# wheatstone.net
KiCad netlist of a schematic drawn in EAGLE
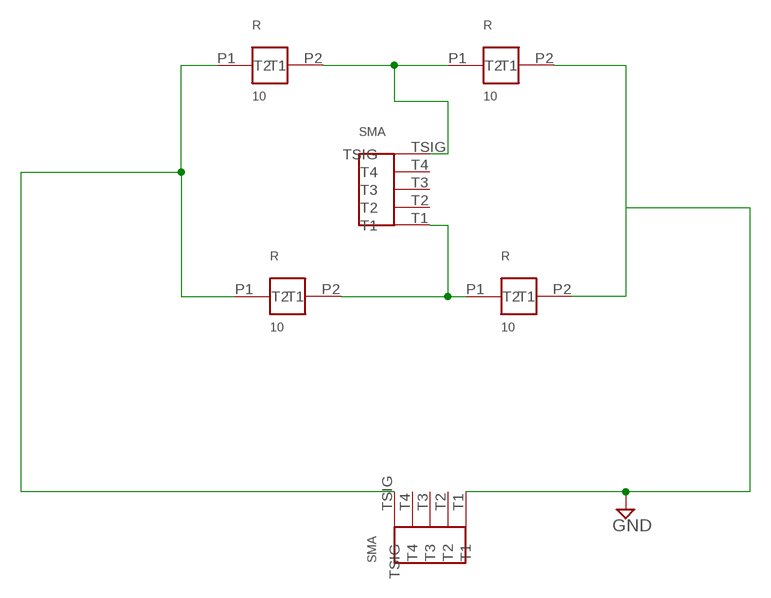
[diagram p0: schematic, sheet 1]

(export (version "E")
  (design (tool "Eeschema 10.0.6"))
  (components
    (comp (ref "U$1")
      (value "0404RESISTORS")
      (footprint "eagle-import:0404RESISTORS")
      (libsource (lib "eagle-import") (part "0404RESISTORS"))
    )
    (comp (ref "U$2")
      (value "0404RESISTORS")
      (footprint "eagle-import:0404RESISTORS")
      (libsource (lib "eagle-import") (part "0404RESISTORS"))
    )
    (comp (ref "U$3")
      (value "0404RESISTORS")
      (footprint "eagle-import:0404RESISTORS")
      (libsource (lib "eagle-import") (part "0404RESISTORS"))
    )
    (comp (ref "U$4")
      (value "0404RESISTORS")
      (footprint "eagle-import:0404RESISTORS")
      (libsource (lib "eagle-import") (part "0404RESISTORS"))
    )
    (comp (ref "U$5") (value "TC") (footprint "eagle-import:TC") (libsource (lib "eagle-import") (part "TC")))
    (comp (ref "U$6") (value "TC") (footprint "eagle-import:TC") (libsource (lib "eagle-import") (part "TC")))
  )
  (nets
    (net (code "1") (name "GND") (class "Default")
      (node (ref "U$2") (pin "P2") (pinfunction "T2_P2") (pintype "bidirectional"))
      (node (ref "U$4") (pin "P2") (pinfunction "T2_P2") (pintype "bidirectional"))
      (node (ref "U$6") (pin "T1") (pinfunction "T1_T1") (pintype "bidirectional"))
    )
    (net (code "2") (name "Net-(U$1-T1)") (class "Default")
      (node (ref "U$1") (pin "P1") (pinfunction "T1_P1") (pintype "bidirectional"))
      (node (ref "U$3") (pin "P1") (pinfunction "T1_P1") (pintype "bidirectional"))
      (node (ref "U$6") (pin "TSIG") (pinfunction "TSIG_TSIG") (pintype "bidirectional"))
    )
    (net (code "3") (name "Net-(U$1-T2)") (class "Default")
      (node (ref "U$1") (pin "P2") (pinfunction "T2_P2") (pintype "bidirectional"))
      (node (ref "U$2") (pin "P1") (pinfunction "T1_P1") (pintype "bidirectional"))
      (node (ref "U$5") (pin "TSIG") (pinfunction "TSIG_TSIG") (pintype "bidirectional"))
    )
    (net (code "4") (name "Net-(U$3-T2)") (class "Default")
      (node (ref "U$3") (pin "P2") (pinfunction "T2_P2") (pintype "bidirectional"))
      (node (ref "U$4") (pin "P1") (pinfunction "T1_P1") (pintype "bidirectional"))
      (node (ref "U$5") (pin "T1") (pinfunction "T1_T1") (pintype "bidirectional"))
    )
    (net (code "5") (name "unconnected-(U$5-PadT2)") (class "Default")
      (node (ref "U$5") (pin "T2") (pinfunction "T2_T2") (pintype "bidirectional"))
    )
    (net (code "6") (name "unconnected-(U$5-PadT3)") (class "Default")
      (node (ref "U$5") (pin "T3") (pinfunction "T3_T3") (pintype "bidirectional"))
    )
    (net (code "7") (name "unconnected-(U$5-PadT4)") (class "Default")
      (node (ref "U$5") (pin "T4") (pinfunction "T4_T4") (pintype "bidirectional"))
    )
    (net (code "8") (name "unconnected-(U$6-PadT2)") (class "Default")
      (node (ref "U$6") (pin "T2") (pinfunction "T2_T2") (pintype "bidirectional"))
    )
    (net (code "9") (name "unconnected-(U$6-PadT3)") (class "Default")
      (node (ref "U$6") (pin "T3") (pinfunction "T3_T3") (pintype "bidirectional"))
    )
    (net (code "10") (name "unconnected-(U$6-PadT4)") (class "Default")
      (node (ref "U$6") (pin "T4") (pinfunction "T4_T4") (pintype "bidirectional"))
    )
  )
)
